# Memory.net
KiCad netlist of a schematic drawn in Altium Designer
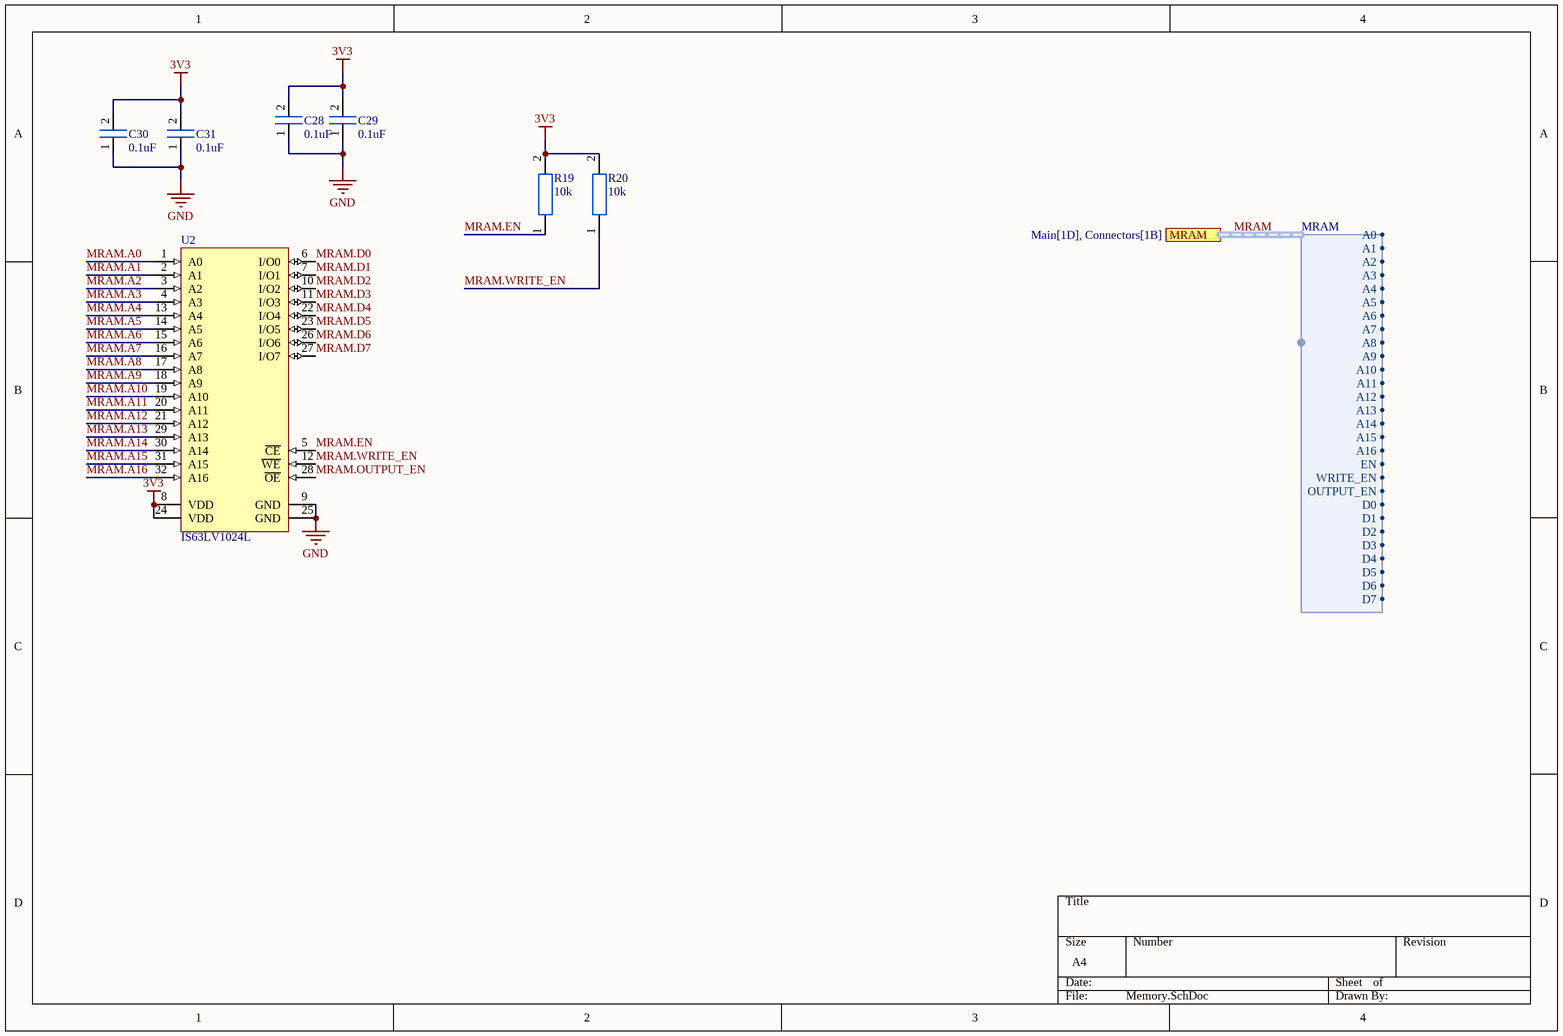
[diagram p0: Memory.SchDoc]

(export (version "E")
  (design (tool "Eeschema 10.0.6"))
  (components
    (comp (ref "C28")
      (value "0.1uF")
      (footprint "0402_footprint")
      (description "0402 capacitor")
      (libsource (lib "Schlib1") (part "Capacitor_0402"))
    )
    (comp (ref "C29")
      (value "0.1uF")
      (footprint "0402_footprint")
      (description "0402 capacitor")
      (libsource (lib "Schlib1") (part "Capacitor_0402"))
    )
    (comp (ref "C30")
      (value "0.1uF")
      (footprint "0402_footprint")
      (description "0402 capacitor")
      (libsource (lib "Schlib1") (part "Capacitor_0402"))
    )
    (comp (ref "C31")
      (value "0.1uF")
      (footprint "0402_footprint")
      (description "0402 capacitor")
      (libsource (lib "Schlib1") (part "Capacitor_0402"))
    )
    (comp (ref "R19")
      (value "10k")
      (footprint "0402_footprint")
      (libsource (lib "Schlib1") (part "Resistor_0402"))
    )
    (comp (ref "R20")
      (value "10k")
      (footprint "0402_footprint")
      (libsource (lib "Schlib1") (part "Resistor_0402"))
    )
    (comp (ref "U2")
      (value "IS63LV1024L")
      (footprint "ISSI-TSOP-2-32_N")
      (fields
        (field (name "MANUFACTURER") "Integrated Silicon Solution Inc (ISSI)")
        (field (name "PARTNUMBER") "IS61WV1288EEBLL-10TLI")
      )
      (libsource (lib "Altium Content Vault") (part "ISSI-IS61WV1288EEBLL-TSOP-2-32"))
    )
  )
  (nets
    (net (code "2") (name "/MRAM.A0") (class "Default")
      (node (ref "U2") (pin "1") (pinfunction "A0_1") (pintype "input"))
    )
    (net (code "3") (name "/MRAM.A1") (class "Default")
      (node (ref "U2") (pin "2") (pinfunction "A1_2") (pintype "input"))
    )
    (net (code "4") (name "/MRAM.A2") (class "Default")
      (node (ref "U2") (pin "3") (pinfunction "A2_3") (pintype "input"))
    )
    (net (code "5") (name "/MRAM.A3") (class "Default")
      (node (ref "U2") (pin "4") (pinfunction "A3_4") (pintype "input"))
    )
    (net (code "6") (name "/MRAM.A4") (class "Default")
      (node (ref "U2") (pin "13") (pinfunction "A4_13") (pintype "input"))
    )
    (net (code "7") (name "/MRAM.A5") (class "Default")
      (node (ref "U2") (pin "14") (pinfunction "A5_14") (pintype "input"))
    )
    (net (code "8") (name "/MRAM.A6") (class "Default")
      (node (ref "U2") (pin "15") (pinfunction "A6_15") (pintype "input"))
    )
    (net (code "9") (name "/MRAM.A7") (class "Default")
      (node (ref "U2") (pin "16") (pinfunction "A7_16") (pintype "input"))
    )
    (net (code "10") (name "/MRAM.A8") (class "Default")
      (node (ref "U2") (pin "17") (pinfunction "A8_17") (pintype "input"))
    )
    (net (code "11") (name "/MRAM.A9") (class "Default")
      (node (ref "U2") (pin "18") (pinfunction "A9_18") (pintype "input"))
    )
    (net (code "12") (name "/MRAM.A10") (class "Default")
      (node (ref "U2") (pin "19") (pinfunction "A10_19") (pintype "input"))
    )
    (net (code "13") (name "/MRAM.A11") (class "Default")
      (node (ref "U2") (pin "20") (pinfunction "A11_20") (pintype "input"))
    )
    (net (code "14") (name "/MRAM.A12") (class "Default")
      (node (ref "U2") (pin "21") (pinfunction "A12_21") (pintype "input"))
    )
    (net (code "15") (name "/MRAM.A13") (class "Default")
      (node (ref "U2") (pin "29") (pinfunction "A13_29") (pintype "input"))
    )
    (net (code "16") (name "/MRAM.A14") (class "Default")
      (node (ref "U2") (pin "30") (pinfunction "A14_30") (pintype "input"))
    )
    (net (code "17") (name "/MRAM.A15") (class "Default")
      (node (ref "U2") (pin "31") (pinfunction "A15_31") (pintype "input"))
    )
    (net (code "18") (name "/MRAM.A16") (class "Default")
      (node (ref "U2") (pin "32") (pinfunction "A16_32") (pintype "input"))
    )
    (net (code "19") (name "/MRAM.D0") (class "Default")
      (node (ref "U2") (pin "6") (pinfunction "I/O0_6") (pintype "bidirectional"))
    )
    (net (code "20") (name "/MRAM.D1") (class "Default")
      (node (ref "U2") (pin "7") (pinfunction "I/O1_7") (pintype "bidirectional"))
    )
    (net (code "21") (name "/MRAM.D2") (class "Default")
      (node (ref "U2") (pin "10") (pinfunction "I/O2_10") (pintype "bidirectional"))
    )
    (net (code "22") (name "/MRAM.D3") (class "Default")
      (node (ref "U2") (pin "11") (pinfunction "I/O3_11") (pintype "bidirectional"))
    )
    (net (code "23") (name "/MRAM.D4") (class "Default")
      (node (ref "U2") (pin "22") (pinfunction "I/O4_22") (pintype "bidirectional"))
    )
    (net (code "24") (name "/MRAM.D5") (class "Default")
      (node (ref "U2") (pin "23") (pinfunction "I/O5_23") (pintype "bidirectional"))
    )
    (net (code "25") (name "/MRAM.D6") (class "Default")
      (node (ref "U2") (pin "26") (pinfunction "I/O6_26") (pintype "bidirectional"))
    )
    (net (code "26") (name "/MRAM.D7") (class "Default")
      (node (ref "U2") (pin "27") (pinfunction "I/O7_27") (pintype "bidirectional"))
    )
    (net (code "27") (name "/MRAM.EN") (class "Default")
      (node (ref "R19") (pin "1") (pinfunction "1_1") (pintype "passive"))
      (node (ref "U2") (pin "5") (pinfunction "~{CE}_5") (pintype "input"))
    )
    (net (code "28") (name "/MRAM.OUTPUT_EN") (class "Default")
      (node (ref "U2") (pin "28") (pinfunction "~{OE}_28") (pintype "input"))
    )
    (net (code "29") (name "/MRAM.WRITE_EN") (class "Default")
      (node (ref "R20") (pin "1") (pinfunction "1_1") (pintype "passive"))
      (node (ref "U2") (pin "12") (pinfunction "~{WE}_12") (pintype "input"))
    )
    (net (code "31") (name "3V3") (class "Default")
      (node (ref "C28") (pin "2") (pinfunction "2_2") (pintype "passive"))
      (node (ref "C29") (pin "2") (pinfunction "2_2") (pintype "passive"))
      (node (ref "C30") (pin "2") (pinfunction "2_2") (pintype "passive"))
      (node (ref "C31") (pin "2") (pinfunction "2_2") (pintype "passive"))
      (node (ref "R19") (pin "2") (pinfunction "2_2") (pintype "passive"))
      (node (ref "R20") (pin "2") (pinfunction "2_2") (pintype "passive"))
      (node (ref "U2") (pin "24") (pinfunction "VDD_24") (pintype "power_in"))
      (node (ref "U2") (pin "8") (pinfunction "VDD_8") (pintype "power_in"))
    )
    (net (code "32") (name "GND") (class "Default")
      (node (ref "C28") (pin "1") (pinfunction "1_1") (pintype "passive"))
      (node (ref "C29") (pin "1") (pinfunction "1_1") (pintype "passive"))
      (node (ref "C30") (pin "1") (pinfunction "1_1") (pintype "passive"))
      (node (ref "C31") (pin "1") (pinfunction "1_1") (pintype "passive"))
      (node (ref "U2") (pin "25") (pinfunction "GND_25") (pintype "power_in"))
      (node (ref "U2") (pin "9") (pinfunction "GND_9") (pintype "power_in"))
    )
  )
)
